# IMU_Motor.net
KiCad netlist of a schematic drawn in Altium Designer
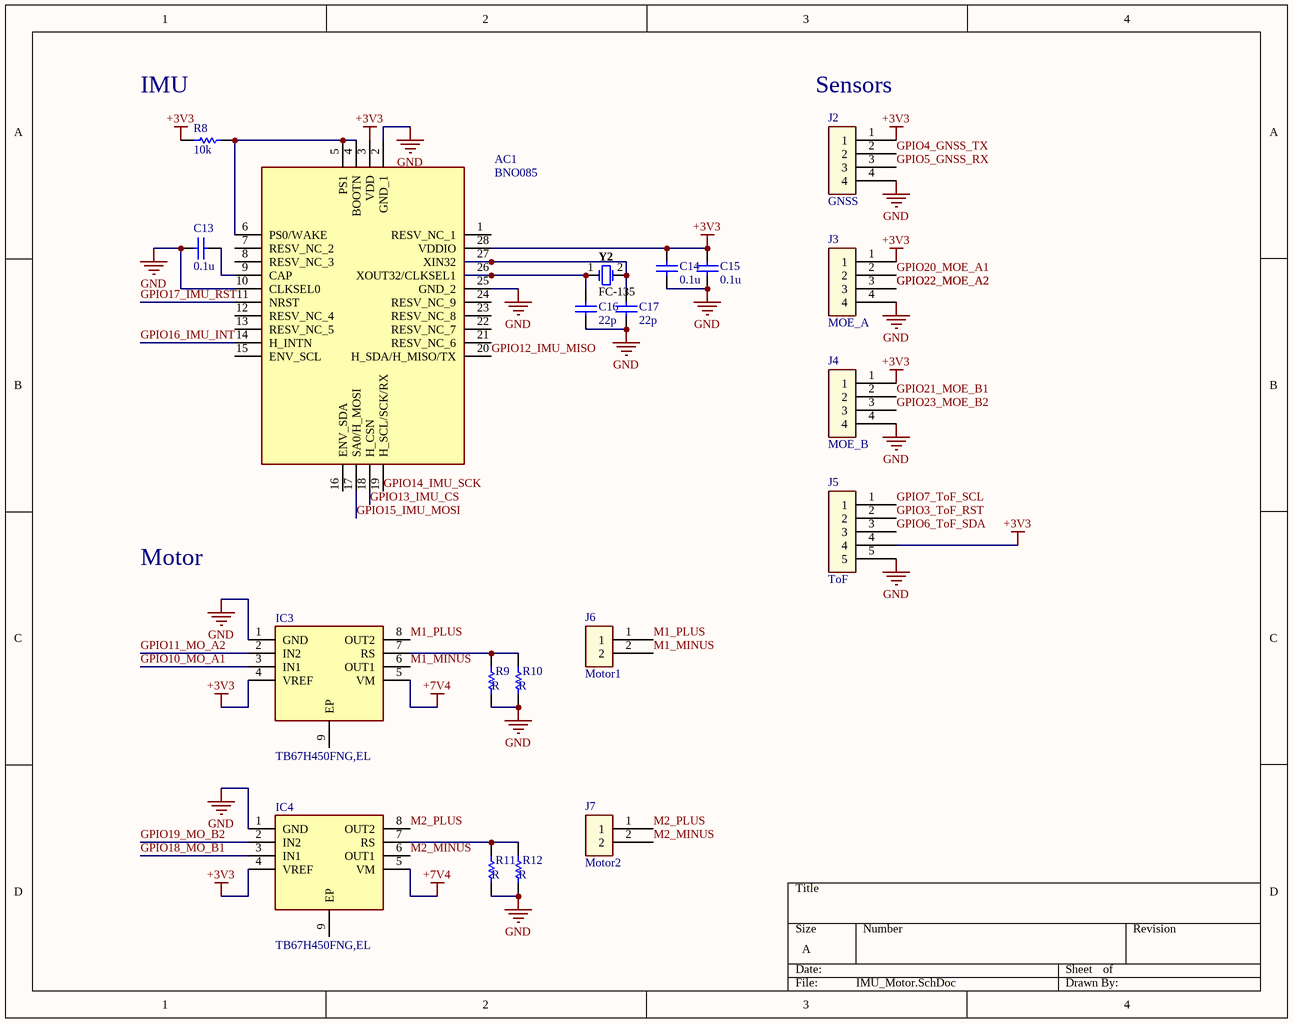
[diagram p0: IMU_Motor.SchDoc]

(export (version "E")
  (design (tool "Eeschema 10.0.6"))
  (components
    (comp (ref "AC1")
      (value "BNO085")
      (footprint "SamacSys:BNO085")
      (description "Accelerometer")
      (libsource (lib "*") (part "BNO085"))
    )
    (comp (ref "C13")
      (value "0.1u")
      (footprint "1608[0603]")
      (description "Capacitor")
      (libsource (lib "Simulation Generic Components") (part "Capacitor"))
    )
    (comp (ref "C14")
      (value "0.1u")
      (footprint "1608[0603]")
      (description "Capacitor")
      (libsource (lib "Simulation Generic Components") (part "Capacitor"))
    )
    (comp (ref "C15")
      (value "0.1u")
      (footprint "1608[0603]")
      (description "Capacitor")
      (libsource (lib "Simulation Generic Components") (part "Capacitor"))
    )
    (comp (ref "C16")
      (value "22p")
      (footprint "1608[0603]")
      (description "Capacitor")
      (libsource (lib "Simulation Generic Components") (part "Capacitor"))
    )
    (comp (ref "C17")
      (value "22p")
      (footprint "1608[0603]")
      (description "Capacitor")
      (libsource (lib "Simulation Generic Components") (part "Capacitor"))
    )
    (comp (ref "IC3")
      (value "TB67H450FNG,EL")
      (footprint "SamacSys:SOIC127P600X175-9N")
      (description "Integrated Circuit")
      (fields (field (name "MOUSER PART NUMBER") "757-TB67H450FNGEL"))
      (libsource (lib "*") (part "TB67H450FNG,EL"))
    )
    (comp (ref "IC4")
      (value "TB67H450FNG,EL")
      (footprint "SamacSys:SOIC127P600X175-9N")
      (description "Integrated Circuit")
      (fields (field (name "MOUSER PART NUMBER") "757-TB67H450FNGEL"))
      (libsource (lib "*") (part "TB67H450FNG,EL"))
    )
    (comp (ref "J2")
      (value "GNSS")
      (footprint "PinHeader_2.0_4_SMD")
      (libsource (lib "tanekonsat_lib") (part "PinHeader_2.0_4_SMD"))
    )
    (comp (ref "J3")
      (value "MOE_A")
      (footprint "PinHeader_2.0_4_SMD")
      (libsource (lib "tanekonsat_lib") (part "PinHeader_2.0_4_SMD"))
    )
    (comp (ref "J4")
      (value "MOE_B")
      (footprint "PinHeader_2.0_4_SMD")
      (libsource (lib "tanekonsat_lib") (part "PinHeader_2.0_4_SMD"))
    )
    (comp (ref "J5")
      (value "ToF")
      (footprint "PinHeader_2.0_5_SMD")
      (libsource (lib "tanekonsat_lib") (part "PinHeader_2.0_5_SMD"))
    )
    (comp (ref "J6")
      (value "Motor1")
      (footprint "PinHeader_2.0_2_SMD")
      (libsource (lib "tanekonsat_lib") (part "PinHeader_2.0_2_SMD"))
    )
    (comp (ref "J7")
      (value "Motor2")
      (footprint "PinHeader_2.0_2_SMD")
      (libsource (lib "tanekonsat_lib") (part "PinHeader_2.0_2_SMD"))
    )
    (comp (ref "R8")
      (value "10k")
      (footprint "1608[0603]")
      (description "Resistor")
      (libsource (lib "Simulation Generic Components") (part "Resistor"))
    )
    (comp (ref "R9")
      (value "R")
      (footprint "1608[0603]")
      (description "Resistor")
      (libsource (lib "Simulation Generic Components") (part "Resistor"))
    )
    (comp (ref "R10")
      (value "R")
      (footprint "1608[0603]")
      (description "Resistor")
      (libsource (lib "Simulation Generic Components") (part "Resistor"))
    )
    (comp (ref "R11")
      (value "R")
      (footprint "1608[0603]")
      (description "Resistor")
      (libsource (lib "Simulation Generic Components") (part "Resistor"))
    )
    (comp (ref "R12")
      (value "R")
      (footprint "1608[0603]")
      (description "Resistor")
      (libsource (lib "Simulation Generic Components") (part "Resistor"))
    )
    (comp (ref "Y2")
      (value "FC-135")
      (footprint "EPSON-FC-135_V")
      (description "Crystal Unit, 32 to 77.5 KHz, 0.5 uW, -40 to 85 degC, 2-Pin SMD, RoHS")
      (fields (field (name "MANUFACTURER") "Epson"))
      (libsource (lib "Altium Content Vault") (part "XTAL-1-2-2"))
    )
  )
  (nets
    (net (code "1") (name "+3V3") (class "Default")
      (node (ref "AC1") (pin "28") (pinfunction "VDDIO_28") (pintype "passive"))
      (node (ref "AC1") (pin "3") (pinfunction "VDD_3") (pintype "passive"))
      (node (ref "C14") (pin "2") (pinfunction "2_2") (pintype "passive"))
      (node (ref "C15") (pin "2") (pinfunction "2_2") (pintype "passive"))
      (node (ref "IC3") (pin "4") (pinfunction "VREF_4") (pintype "passive"))
      (node (ref "IC4") (pin "4") (pinfunction "VREF_4") (pintype "passive"))
      (node (ref "J2") (pin "1") (pinfunction "1_1") (pintype "passive"))
      (node (ref "J3") (pin "1") (pinfunction "1_1") (pintype "passive"))
      (node (ref "J4") (pin "1") (pinfunction "1_1") (pintype "passive"))
      (node (ref "J5") (pin "4") (pinfunction "4_4") (pintype "passive"))
      (node (ref "R8") (pin "1") (pinfunction "1_1") (pintype "passive"))
    )
    (net (code "2") (name "+7V4") (class "Default")
      (node (ref "IC3") (pin "5") (pinfunction "VM_5") (pintype "passive"))
      (node (ref "IC4") (pin "5") (pinfunction "VM_5") (pintype "passive"))
    )
    (net (code "3") (name "/GPIO3_ToF_RST") (class "Default")
      (node (ref "J5") (pin "2") (pinfunction "2_2") (pintype "passive"))
    )
    (net (code "4") (name "/GPIO4_GNSS_TX") (class "Default")
      (node (ref "J2") (pin "2") (pinfunction "2_2") (pintype "passive"))
    )
    (net (code "5") (name "/GPIO5_GNSS_RX") (class "Default")
      (node (ref "J2") (pin "3") (pinfunction "3_3") (pintype "passive"))
    )
    (net (code "6") (name "/GPIO6_ToF_SDA") (class "Default")
      (node (ref "J5") (pin "3") (pinfunction "3_3") (pintype "passive"))
    )
    (net (code "7") (name "/GPIO7_ToF_SCL") (class "Default")
      (node (ref "J5") (pin "1") (pinfunction "1_1") (pintype "passive"))
    )
    (net (code "8") (name "/GPIO10_MO_A1") (class "Default")
      (node (ref "IC3") (pin "3") (pinfunction "IN1_3") (pintype "passive"))
    )
    (net (code "9") (name "/GPIO11_MO_A2") (class "Default")
      (node (ref "IC3") (pin "2") (pinfunction "IN2_2") (pintype "passive"))
    )
    (net (code "10") (name "/GPIO12_IMU_MISO") (class "Default")
      (node (ref "AC1") (pin "20") (pinfunction "H_SDA/H_MISO/TX_20") (pintype "passive"))
    )
    (net (code "11") (name "/GPIO13_IMU_CS") (class "Default")
      (node (ref "AC1") (pin "18") (pinfunction "H_CSN_18") (pintype "passive"))
    )
    (net (code "12") (name "/GPIO14_IMU_SCK") (class "Default")
      (node (ref "AC1") (pin "19") (pinfunction "H_SCL/SCK/RX_19") (pintype "passive"))
    )
    (net (code "13") (name "/GPIO15_IMU_MOSI") (class "Default")
      (node (ref "AC1") (pin "17") (pinfunction "SA0/H_MOSI_17") (pintype "passive"))
    )
    (net (code "14") (name "/GPIO16_IMU_INT") (class "Default")
      (node (ref "AC1") (pin "14") (pinfunction "H_INTN_14") (pintype "passive"))
    )
    (net (code "15") (name "/GPIO17_IMU_RST") (class "Default")
      (node (ref "AC1") (pin "11") (pinfunction "NRST_11") (pintype "passive"))
    )
    (net (code "16") (name "/GPIO18_MO_B1") (class "Default")
      (node (ref "IC4") (pin "3") (pinfunction "IN1_3") (pintype "passive"))
    )
    (net (code "17") (name "/GPIO19_MO_B2") (class "Default")
      (node (ref "IC4") (pin "2") (pinfunction "IN2_2") (pintype "passive"))
    )
    (net (code "18") (name "/GPIO20_MOE_A1") (class "Default")
      (node (ref "J3") (pin "2") (pinfunction "2_2") (pintype "passive"))
    )
    (net (code "19") (name "/GPIO21_MOE_B1") (class "Default")
      (node (ref "J4") (pin "2") (pinfunction "2_2") (pintype "passive"))
    )
    (net (code "20") (name "/GPIO22_MOE_A2") (class "Default")
      (node (ref "J3") (pin "3") (pinfunction "3_3") (pintype "passive"))
    )
    (net (code "21") (name "/GPIO23_MOE_B2") (class "Default")
      (node (ref "J4") (pin "3") (pinfunction "3_3") (pintype "passive"))
    )
    (net (code "22") (name "/M1_MINUS") (class "Default")
      (node (ref "IC3") (pin "6") (pinfunction "OUT1_6") (pintype "passive"))
      (node (ref "J6") (pin "2") (pinfunction "2_2") (pintype "passive"))
    )
    (net (code "23") (name "/M1_PLUS") (class "Default")
      (node (ref "IC3") (pin "8") (pinfunction "OUT2_8") (pintype "passive"))
      (node (ref "J6") (pin "1") (pinfunction "1_1") (pintype "passive"))
    )
    (net (code "24") (name "/M2_MINUS") (class "Default")
      (node (ref "IC4") (pin "6") (pinfunction "OUT1_6") (pintype "passive"))
      (node (ref "J7") (pin "2") (pinfunction "2_2") (pintype "passive"))
    )
    (net (code "25") (name "/M2_PLUS") (class "Default")
      (node (ref "IC4") (pin "8") (pinfunction "OUT2_8") (pintype "passive"))
      (node (ref "J7") (pin "1") (pinfunction "1_1") (pintype "passive"))
    )
    (net (code "26") (name "GND") (class "Default")
      (node (ref "AC1") (pin "10") (pinfunction "CLKSEL0_10") (pintype "passive"))
      (node (ref "AC1") (pin "2") (pinfunction "GND_1_2") (pintype "passive"))
      (node (ref "AC1") (pin "25") (pinfunction "GND_2_25") (pintype "passive"))
      (node (ref "C13") (pin "1") (pinfunction "1_1") (pintype "passive"))
      (node (ref "C14") (pin "1") (pinfunction "1_1") (pintype "passive"))
      (node (ref "C15") (pin "1") (pinfunction "1_1") (pintype "passive"))
      (node (ref "C16") (pin "1") (pinfunction "1_1") (pintype "passive"))
      (node (ref "C17") (pin "1") (pinfunction "1_1") (pintype "passive"))
      (node (ref "IC3") (pin "1") (pinfunction "GND_1") (pintype "passive"))
      (node (ref "IC4") (pin "1") (pinfunction "GND_1") (pintype "passive"))
      (node (ref "J2") (pin "4") (pinfunction "4_4") (pintype "passive"))
      (node (ref "J3") (pin "4") (pinfunction "4_4") (pintype "passive"))
      (node (ref "J4") (pin "4") (pinfunction "4_4") (pintype "passive"))
      (node (ref "J5") (pin "5") (pinfunction "5_5") (pintype "passive"))
      (node (ref "R10") (pin "1") (pinfunction "1_1") (pintype "passive"))
      (node (ref "R11") (pin "1") (pinfunction "1_1") (pintype "passive"))
      (node (ref "R12") (pin "1") (pinfunction "1_1") (pintype "passive"))
      (node (ref "R9") (pin "1") (pinfunction "1_1") (pintype "passive"))
    )
    (net (code "27") (name "Net-(AC1-BOOTN)") (class "Default")
      (node (ref "AC1") (pin "4") (pinfunction "BOOTN_4") (pintype "passive"))
      (node (ref "AC1") (pin "5") (pinfunction "PS1_5") (pintype "passive"))
      (node (ref "AC1") (pin "6") (pinfunction "PS0/WAKE_6") (pintype "passive"))
      (node (ref "R8") (pin "2") (pinfunction "2_2") (pintype "passive"))
    )
    (net (code "28") (name "Net-(AC1-CAP)") (class "Default")
      (node (ref "AC1") (pin "9") (pinfunction "CAP_9") (pintype "passive"))
      (node (ref "C13") (pin "2") (pinfunction "2_2") (pintype "passive"))
    )
    (net (code "29") (name "Net-(AC1-XIN32)") (class "Default")
      (node (ref "AC1") (pin "27") (pinfunction "XIN32_27") (pintype "passive"))
      (node (ref "C17") (pin "2") (pinfunction "2_2") (pintype "passive"))
      (node (ref "Y2") (pin "2") (pinfunction "2_2") (pintype "passive"))
    )
    (net (code "30") (name "Net-(AC1-XOUT32{slash}CLKSEL1)") (class "Default")
      (node (ref "AC1") (pin "26") (pinfunction "XOUT32/CLKSEL1_26") (pintype "passive"))
      (node (ref "C16") (pin "2") (pinfunction "2_2") (pintype "passive"))
      (node (ref "Y2") (pin "1") (pinfunction "1_1") (pintype "passive"))
    )
    (net (code "31") (name "Net-(IC3-RS)") (class "Default")
      (node (ref "IC3") (pin "7") (pinfunction "RS_7") (pintype "passive"))
      (node (ref "R10") (pin "2") (pinfunction "2_2") (pintype "passive"))
      (node (ref "R9") (pin "2") (pinfunction "2_2") (pintype "passive"))
    )
    (net (code "32") (name "Net-(IC4-RS)") (class "Default")
      (node (ref "IC4") (pin "7") (pinfunction "RS_7") (pintype "passive"))
      (node (ref "R11") (pin "2") (pinfunction "2_2") (pintype "passive"))
      (node (ref "R12") (pin "2") (pinfunction "2_2") (pintype "passive"))
    )
    (net (code "33") (name "unconnected-(AC1-ENV_SCL-Pad15)") (class "Default")
      (node (ref "AC1") (pin "15") (pinfunction "ENV_SCL_15") (pintype "passive"))
    )
    (net (code "34") (name "unconnected-(AC1-ENV_SDA-Pad16)") (class "Default")
      (node (ref "AC1") (pin "16") (pinfunction "ENV_SDA_16") (pintype "passive"))
    )
    (net (code "35") (name "unconnected-(AC1-RESV_NC_1-Pad1)") (class "Default")
      (node (ref "AC1") (pin "1") (pinfunction "RESV_NC_1_1") (pintype "passive"))
    )
    (net (code "36") (name "unconnected-(AC1-RESV_NC_2-Pad7)") (class "Default")
      (node (ref "AC1") (pin "7") (pinfunction "RESV_NC_2_7") (pintype "passive"))
    )
    (net (code "37") (name "unconnected-(AC1-RESV_NC_3-Pad8)") (class "Default")
      (node (ref "AC1") (pin "8") (pinfunction "RESV_NC_3_8") (pintype "passive"))
    )
    (net (code "38") (name "unconnected-(AC1-RESV_NC_4-Pad12)") (class "Default")
      (node (ref "AC1") (pin "12") (pinfunction "RESV_NC_4_12") (pintype "passive"))
    )
    (net (code "39") (name "unconnected-(AC1-RESV_NC_5-Pad13)") (class "Default")
      (node (ref "AC1") (pin "13") (pinfunction "RESV_NC_5_13") (pintype "passive"))
    )
    (net (code "40") (name "unconnected-(AC1-RESV_NC_6-Pad21)") (class "Default")
      (node (ref "AC1") (pin "21") (pinfunction "RESV_NC_6_21") (pintype "passive"))
    )
    (net (code "41") (name "unconnected-(AC1-RESV_NC_7-Pad22)") (class "Default")
      (node (ref "AC1") (pin "22") (pinfunction "RESV_NC_7_22") (pintype "passive"))
    )
    (net (code "42") (name "unconnected-(AC1-RESV_NC_8-Pad23)") (class "Default")
      (node (ref "AC1") (pin "23") (pinfunction "RESV_NC_8_23") (pintype "passive"))
    )
    (net (code "43") (name "unconnected-(AC1-RESV_NC_9-Pad24)") (class "Default")
      (node (ref "AC1") (pin "24") (pinfunction "RESV_NC_9_24") (pintype "passive"))
    )
    (net (code "44") (name "unconnected-(IC3-EP-Pad9)") (class "Default")
      (node (ref "IC3") (pin "9") (pinfunction "EP_9") (pintype "passive"))
    )
    (net (code "45") (name "unconnected-(IC4-EP-Pad9)") (class "Default")
      (node (ref "IC4") (pin "9") (pinfunction "EP_9") (pintype "passive"))
    )
  )
)
